# Polarshield_v2_5.net
KiCad netlist of a schematic drawn in EAGLE
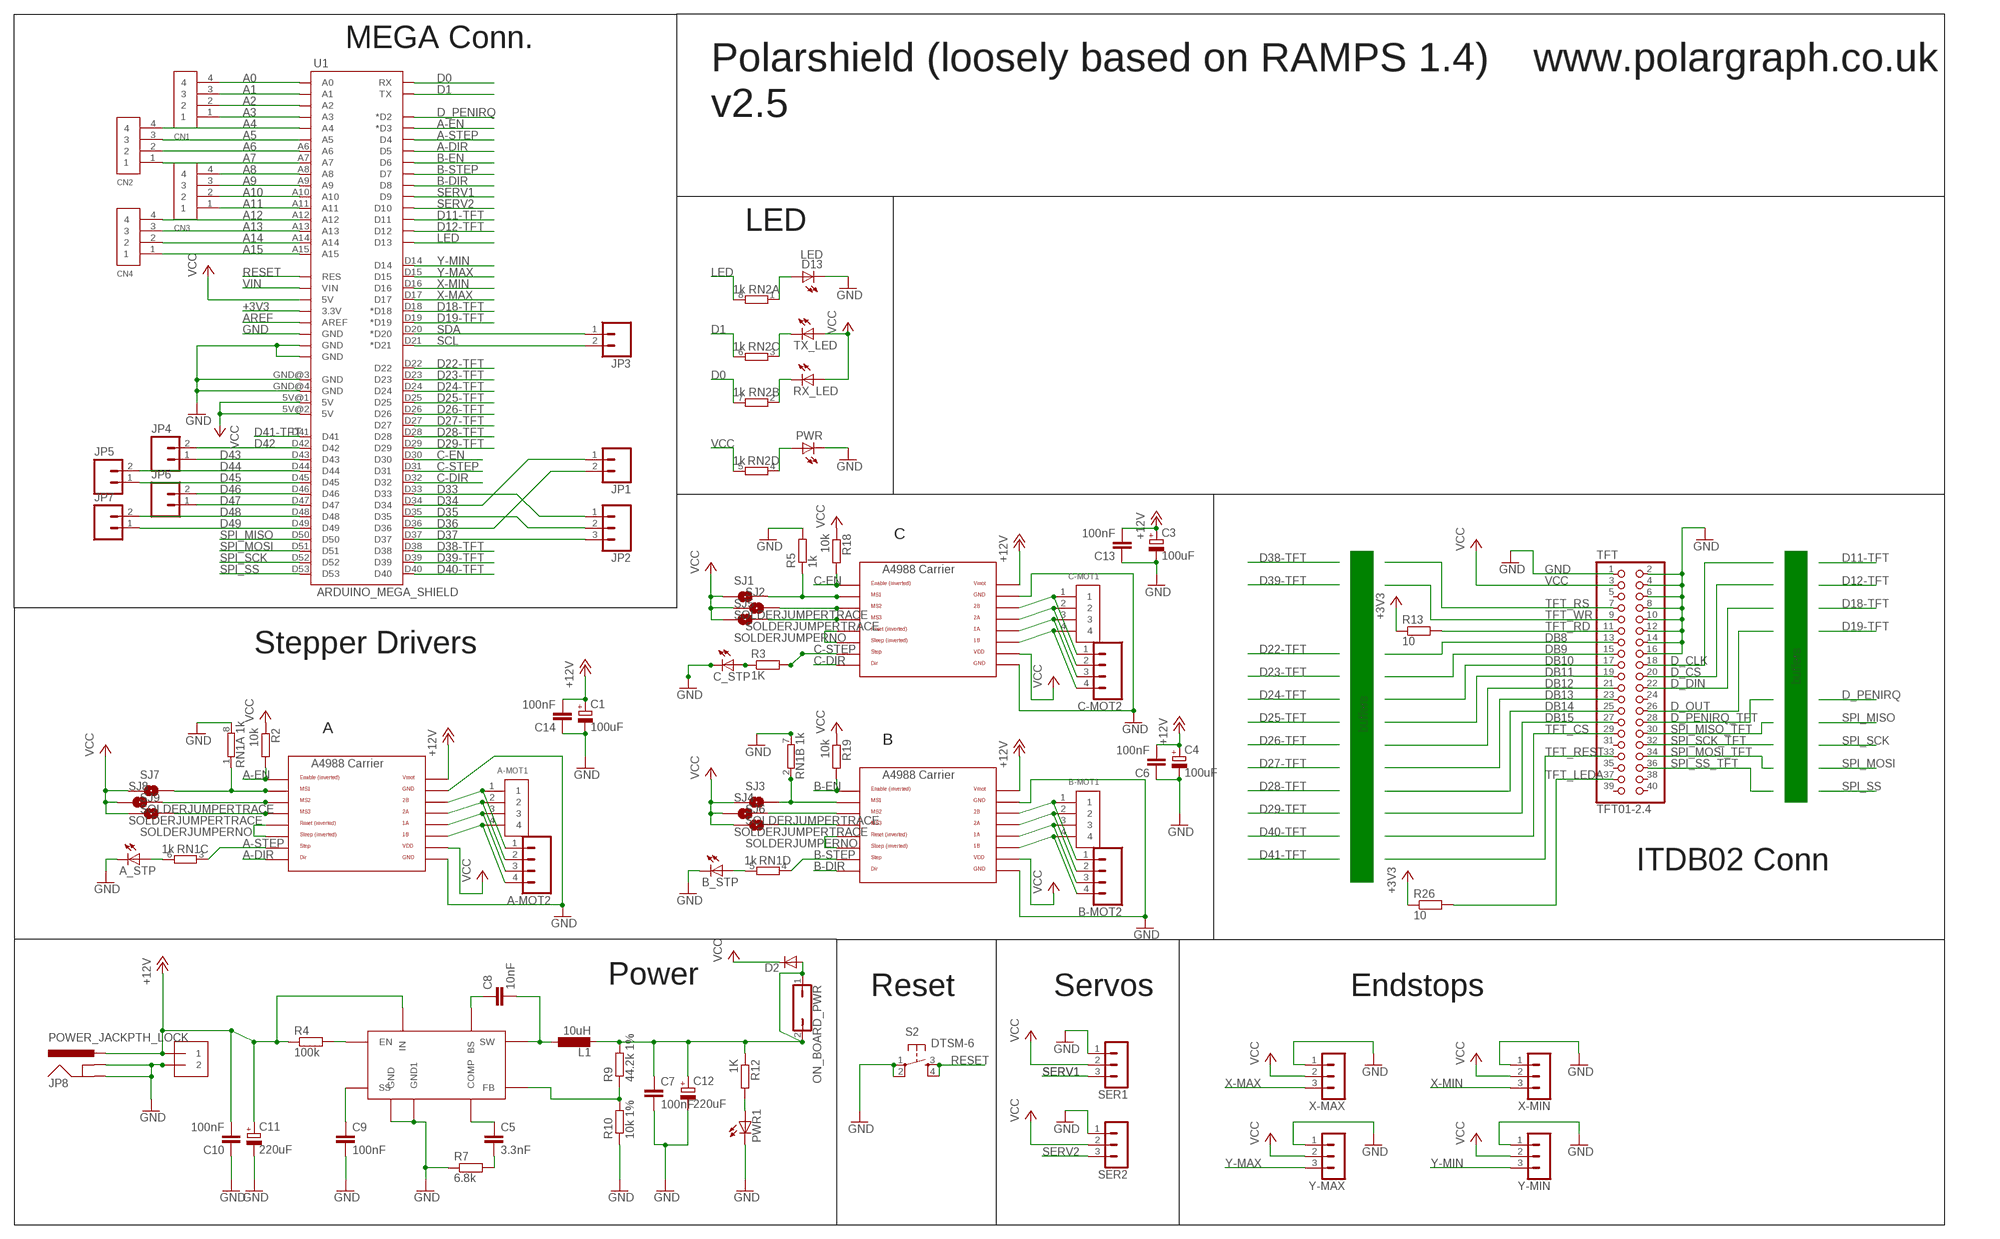
[diagram p0: schematic, sheet 1, part 1 of 2]
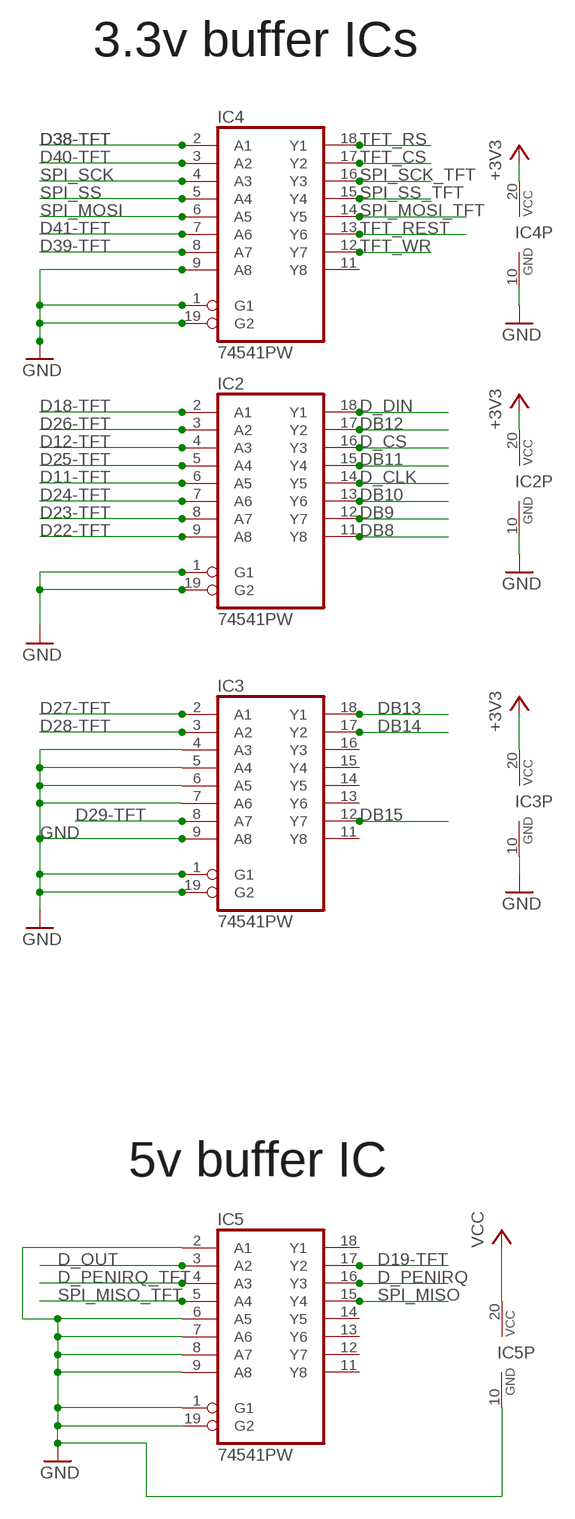
[diagram p1: schematic, sheet 1, part 2 of 2]

(export (version "E")
  (design (tool "Eeschema 10.0.6"))
  (components
    (comp (ref "A-MOT1")
      (value "1X4-BIG")
      (footprint "eagle-import:1X04-BIG")
      (libsource (lib "eagle-import") (part "adafruit_1X4-BIG"))
    )
    (comp (ref "A-MOT2")
      (value "M04SCREW")
      (footprint "eagle-import:SCREWTERMINAL-3.5MM-4")
      (libsource (lib "eagle-import") (part "M04SCREW"))
    )
    (comp (ref "A_STP")
      (value "LEDCHIP-LED0805")
      (footprint "eagle-import:CHIP-LED0805")
      (libsource (lib "eagle-import") (part "LEDCHIP-LED0805"))
    )
    (comp (ref "B-MOT1")
      (value "1X4-BIG")
      (footprint "eagle-import:1X04-BIG")
      (libsource (lib "eagle-import") (part "adafruit_1X4-BIG"))
    )
    (comp (ref "B-MOT2")
      (value "M04SCREW")
      (footprint "eagle-import:SCREWTERMINAL-3.5MM-4")
      (libsource (lib "eagle-import") (part "M04SCREW"))
    )
    (comp (ref "B_STP")
      (value "LEDCHIP-LED0805")
      (footprint "eagle-import:CHIP-LED0805")
      (libsource (lib "eagle-import") (part "LEDCHIP-LED0805"))
    )
    (comp (ref "C-MOT1")
      (value "1X4-BIG")
      (footprint "eagle-import:1X04-BIG")
      (libsource (lib "eagle-import") (part "adafruit_1X4-BIG"))
    )
    (comp (ref "C-MOT2")
      (value "M04SCREW")
      (footprint "eagle-import:SCREWTERMINAL-3.5MM-4")
      (libsource (lib "eagle-import") (part "M04SCREW"))
    )
    (comp (ref "C1")
      (value "100uF")
      (footprint "eagle-import:153CLV-0605")
      (libsource (lib "eagle-import") (part "CPOL-EU153CLV-0605"))
    )
    (comp (ref "C3")
      (value "100uF")
      (footprint "eagle-import:153CLV-0605")
      (libsource (lib "eagle-import") (part "CPOL-EU153CLV-0605"))
    )
    (comp (ref "C4")
      (value "100uF")
      (footprint "eagle-import:153CLV-0605")
      (libsource (lib "eagle-import") (part "CPOL-EU153CLV-0605"))
    )
    (comp (ref "C5")
      (value "3.3nF")
      (footprint "eagle-import:C0805K")
      (libsource (lib "eagle-import") (part "C-EUC0805K"))
    )
    (comp (ref "C6")
      (value "100nF")
      (footprint "eagle-import:C0805")
      (libsource (lib "eagle-import") (part "C-EUC0805"))
    )
    (comp (ref "C7")
      (value "100nF")
      (footprint "eagle-import:C0805K")
      (libsource (lib "eagle-import") (part "C-EUC0805K"))
    )
    (comp (ref "C8")
      (value "10nF")
      (footprint "eagle-import:C0805K")
      (libsource (lib "eagle-import") (part "C-EUC0805K"))
    )
    (comp (ref "C9")
      (value "100nF")
      (footprint "eagle-import:C0805K")
      (libsource (lib "eagle-import") (part "C-EUC0805K"))
    )
    (comp (ref "C10")
      (value "100nF")
      (footprint "eagle-import:C0805K")
      (libsource (lib "eagle-import") (part "C-EUC0805K"))
    )
    (comp (ref "C11")
      (value "220uF")
      (footprint "eagle-import:153CLV-0807")
      (libsource (lib "eagle-import") (part "resistor_CPOL-EU153CLV-0807"))
    )
    (comp (ref "C12")
      (value "220uF")
      (footprint "eagle-import:153CLV-0807")
      (libsource (lib "eagle-import") (part "resistor_CPOL-EU153CLV-0807"))
    )
    (comp (ref "C13")
      (value "100nF")
      (footprint "eagle-import:C0805")
      (libsource (lib "eagle-import") (part "C-EUC0805"))
    )
    (comp (ref "C14")
      (value "100nF")
      (footprint "eagle-import:C0805")
      (libsource (lib "eagle-import") (part "C-EUC0805"))
    )
    (comp (ref "CN1")
      (value "1X4-CLEANBIG")
      (footprint "eagle-import:1X04-CLEANBIG")
      (libsource (lib "eagle-import") (part "1X4-CLEANBIG"))
    )
    (comp (ref "CN2")
      (value "1X4-CLEANBIG")
      (footprint "eagle-import:1X04-CLEANBIG")
      (libsource (lib "eagle-import") (part "1X4-CLEANBIG"))
    )
    (comp (ref "CN3")
      (value "1X4-CLEANBIG")
      (footprint "eagle-import:1X04-CLEANBIG")
      (libsource (lib "eagle-import") (part "1X4-CLEANBIG"))
    )
    (comp (ref "CN4")
      (value "1X4-CLEANBIG")
      (footprint "eagle-import:1X04-CLEANBIG")
      (libsource (lib "eagle-import") (part "1X4-CLEANBIG"))
    )
    (comp (ref "C_STP")
      (value "LEDCHIP-LED0805")
      (footprint "eagle-import:CHIP-LED0805")
      (libsource (lib "eagle-import") (part "LEDCHIP-LED0805"))
    )
    (comp (ref "D2")
      (value "DIODE-DO214BA")
      (footprint "eagle-import:DO214BA")
      (libsource (lib "eagle-import") (part "DIODE-DO214BA"))
    )
    (comp (ref "D13")
      (value "LED")
      (footprint "eagle-import:CHIP-LED0805")
      (libsource (lib "eagle-import") (part "LEDCHIP-LED0805"))
    )
    (comp (ref "IC1")
      (value "MP2307")
      (footprint "eagle-import:SOIC8")
      (libsource (lib "eagle-import") (part "MP2307"))
    )
    (comp (ref "IC2")
      (value "74541PW")
      (footprint "eagle-import:TSSOP20")
      (libsource (lib "eagle-import") (part "74541PW"))
    )
    (comp (ref "IC3")
      (value "74541PW")
      (footprint "eagle-import:TSSOP20")
      (libsource (lib "eagle-import") (part "74541PW"))
    )
    (comp (ref "IC4")
      (value "74541PW")
      (footprint "eagle-import:TSSOP20")
      (libsource (lib "eagle-import") (part "74541PW"))
    )
    (comp (ref "IC5")
      (value "74541PW")
      (footprint "eagle-import:TSSOP20")
      (libsource (lib "eagle-import") (part "74541PW"))
    )
    (comp (ref "J1")
      (value "1X2-3.5MM")
      (footprint "eagle-import:1X2-3.5MM")
      (libsource (lib "eagle-import") (part "1X2-3.5MM"))
    )
    (comp (ref "JP1")
      (value "M021X02_NO_SILK")
      (footprint "eagle-import:1X02_NO_SILK")
      (libsource (lib "eagle-import") (part "M021X02_NO_SILK"))
    )
    (comp (ref "JP2")
      (value "M031X03_NO_SILK")
      (footprint "eagle-import:1X03_NO_SILK")
      (libsource (lib "eagle-import") (part "M031X03_NO_SILK"))
    )
    (comp (ref "JP3")
      (value "M021X02_NO_SILK")
      (footprint "eagle-import:1X02_NO_SILK")
      (libsource (lib "eagle-import") (part "M021X02_NO_SILK"))
    )
    (comp (ref "JP4")
      (value "M021X02_NO_SILK")
      (footprint "eagle-import:1X02_NO_SILK")
      (libsource (lib "eagle-import") (part "M021X02_NO_SILK"))
    )
    (comp (ref "JP5")
      (value "M021X02_NO_SILK")
      (footprint "eagle-import:1X02_NO_SILK")
      (libsource (lib "eagle-import") (part "M021X02_NO_SILK"))
    )
    (comp (ref "JP6")
      (value "M021X02_NO_SILK")
      (footprint "eagle-import:1X02_NO_SILK")
      (libsource (lib "eagle-import") (part "M021X02_NO_SILK"))
    )
    (comp (ref "JP7")
      (value "M021X02_NO_SILK")
      (footprint "eagle-import:1X02_NO_SILK")
      (libsource (lib "eagle-import") (part "M021X02_NO_SILK"))
    )
    (comp (ref "JP8")
      (value "POWER_JACKPTH_LOCK")
      (footprint "eagle-import:POWER_JACK_PTH_LOCK")
      (libsource (lib "eagle-import") (part "POWER_JACKPTH_LOCK"))
    )
    (comp (ref "L1")
      (value "10uH")
      (footprint "eagle-import:PIS2816")
      (libsource (lib "eagle-import") (part "L-EUPIS2816"))
    )
    (comp (ref "ON_BOARD_PWR")
      (value "JP1Q")
      (footprint "eagle-import:JP1")
      (libsource (lib "eagle-import") (part "JP1Q"))
    )
    (comp (ref "PWR")
      (value "LEDCHIP-LED0805")
      (footprint "eagle-import:CHIP-LED0805")
      (libsource (lib "eagle-import") (part "LEDCHIP-LED0805"))
    )
    (comp (ref "PWR1")
      (value "LEDCHIP-LED0805")
      (footprint "eagle-import:CHIP-LED0805")
      (libsource (lib "eagle-import") (part "LEDCHIP-LED0805"))
    )
    (comp (ref "R2")
      (value "10k")
      (footprint "eagle-import:R0805")
      (libsource (lib "eagle-import") (part "R-EU_R0805"))
    )
    (comp (ref "R3")
      (value "1K")
      (footprint "eagle-import:R0805")
      (libsource (lib "eagle-import") (part "R-EU_R0805"))
    )
    (comp (ref "R4")
      (value "100k")
      (footprint "eagle-import:R0805")
      (libsource (lib "eagle-import") (part "resistor_R-EU_R0805"))
    )
    (comp (ref "R5")
      (value "1k")
      (footprint "eagle-import:R0805")
      (libsource (lib "eagle-import") (part "R-EU_R0805"))
    )
    (comp (ref "R7")
      (value "6.8k")
      (footprint "eagle-import:R0805")
      (libsource (lib "eagle-import") (part "resistor_R-EU_R0805"))
    )
    (comp (ref "R9")
      (value "44.2k 1%")
      (footprint "eagle-import:R0805")
      (libsource (lib "eagle-import") (part "resistor_R-EU_R0805"))
    )
    (comp (ref "R10")
      (value "10k 1%")
      (footprint "eagle-import:R0805")
      (libsource (lib "eagle-import") (part "resistor_R-EU_R0805"))
    )
    (comp (ref "R12")
      (value "1K")
      (footprint "eagle-import:R0805")
      (libsource (lib "eagle-import") (part "R-EU_R0805"))
    )
    (comp (ref "R13")
      (value "10")
      (footprint "eagle-import:R0805")
      (libsource (lib "eagle-import") (part "resistor_R-EU_R0805"))
    )
    (comp (ref "R18")
      (value "10k")
      (footprint "eagle-import:R0805")
      (libsource (lib "eagle-import") (part "R-EU_R0805"))
    )
    (comp (ref "R19")
      (value "10k")
      (footprint "eagle-import:R0805")
      (libsource (lib "eagle-import") (part "R-EU_R0805"))
    )
    (comp (ref "R26")
      (value "10")
      (footprint "eagle-import:R0805")
      (libsource (lib "eagle-import") (part "resistor_R-EU_R0805"))
    )
    (comp (ref "RN1")
      (value "1k")
      (footprint "eagle-import:EXBN8V")
      (libsource (lib "eagle-import") (part "4R-NEXBN8V"))
    )
    (comp (ref "RN2")
      (value "1k")
      (footprint "eagle-import:EXBN8V")
      (libsource (lib "eagle-import") (part "4R-NEXBN8V"))
    )
    (comp (ref "RX_LED")
      (value "LEDCHIP-LED0805")
      (footprint "eagle-import:CHIP-LED0805")
      (libsource (lib "eagle-import") (part "LEDCHIP-LED0805"))
    )
    (comp (ref "S2")
      (value "DTSM-6")
      (footprint "eagle-import:DTSM-6")
      (libsource (lib "eagle-import") (part "DTSM-6"))
    )
    (comp (ref "SER1")
      (value "3PIN-HEADER")
      (footprint "eagle-import:3PIN-HEADER")
      (libsource (lib "eagle-import") (part "3PIN-HEADER"))
    )
    (comp (ref "SER2")
      (value "3PIN-HEADER")
      (footprint "eagle-import:3PIN-HEADER")
      (libsource (lib "eagle-import") (part "3PIN-HEADER"))
    )
    (comp (ref "SJ1")
      (value "SOLDERJUMPERTRACE")
      (footprint "eagle-import:SJ_2S-TRACE")
      (libsource (lib "eagle-import") (part "SOLDERJUMPERTRACE"))
    )
    (comp (ref "SJ2")
      (value "SOLDERJUMPERTRACE")
      (footprint "eagle-import:SJ_2S-TRACE")
      (libsource (lib "eagle-import") (part "SOLDERJUMPERTRACE"))
    )
    (comp (ref "SJ3")
      (value "SOLDERJUMPERTRACE")
      (footprint "eagle-import:SJ_2S-TRACE")
      (libsource (lib "eagle-import") (part "SOLDERJUMPERTRACE"))
    )
    (comp (ref "SJ4")
      (value "SOLDERJUMPERTRACE")
      (footprint "eagle-import:SJ_2S-TRACE")
      (libsource (lib "eagle-import") (part "SOLDERJUMPERTRACE"))
    )
    (comp (ref "SJ5")
      (value "SOLDERJUMPERNO")
      (footprint "eagle-import:SJ_2S-NO")
      (libsource (lib "eagle-import") (part "SOLDERJUMPERNO"))
    )
    (comp (ref "SJ6")
      (value "SOLDERJUMPERNO")
      (footprint "eagle-import:SJ_2S-NO")
      (libsource (lib "eagle-import") (part "SOLDERJUMPERNO"))
    )
    (comp (ref "SJ7")
      (value "SOLDERJUMPERTRACE")
      (footprint "eagle-import:SJ_2S-TRACE")
      (libsource (lib "eagle-import") (part "SOLDERJUMPERTRACE"))
    )
    (comp (ref "SJ8")
      (value "SOLDERJUMPERTRACE")
      (footprint "eagle-import:SJ_2S-TRACE")
      (libsource (lib "eagle-import") (part "SOLDERJUMPERTRACE"))
    )
    (comp (ref "SJ9")
      (value "SOLDERJUMPERNO")
      (footprint "eagle-import:SJ_2S-NO")
      (libsource (lib "eagle-import") (part "SOLDERJUMPERNO"))
    )
    (comp (ref "TFT")
      (value "TFT01-2.4")
      (footprint "eagle-import:TFT01-2.4")
      (libsource (lib "eagle-import") (part "TFT01-2.4"))
    )
    (comp (ref "TX_LED")
      (value "LEDCHIP-LED0805")
      (footprint "eagle-import:CHIP-LED0805")
      (libsource (lib "eagle-import") (part "LEDCHIP-LED0805"))
    )
    (comp (ref "U$1")
      (value "A4988BREAKOUT")
      (footprint "eagle-import:A4988BREAKOUT")
      (libsource (lib "eagle-import") (part "A4988BREAKOUT"))
    )
    (comp (ref "U$6")
      (value "A4988BREAKOUT")
      (footprint "eagle-import:A4988BREAKOUT")
      (libsource (lib "eagle-import") (part "A4988BREAKOUT"))
    )
    (comp (ref "U$7")
      (value "A4988BREAKOUT")
      (footprint "eagle-import:A4988BREAKOUT")
      (libsource (lib "eagle-import") (part "A4988BREAKOUT"))
    )
    (comp (ref "U1")
      (value "ARDUINO_MEGA_SHIELD")
      (footprint "eagle-import:ARDUINO_MEGA_SHIELD")
      (libsource (lib "eagle-import") (part "ARDUINO_MEGA_SHIELD"))
    )
    (comp (ref "X-MAX")
      (value "3PIN-HEADER")
      (footprint "eagle-import:3PIN-HEADER")
      (libsource (lib "eagle-import") (part "3PIN-HEADER"))
    )
    (comp (ref "X-MIN")
      (value "3PIN-HEADER")
      (footprint "eagle-import:3PIN-HEADER")
      (libsource (lib "eagle-import") (part "3PIN-HEADER"))
    )
    (comp (ref "Y-MAX")
      (value "3PIN-HEADER")
      (footprint "eagle-import:3PIN-HEADER")
      (libsource (lib "eagle-import") (part "3PIN-HEADER"))
    )
    (comp (ref "Y-MIN")
      (value "3PIN-HEADER")
      (footprint "eagle-import:3PIN-HEADER")
      (libsource (lib "eagle-import") (part "3PIN-HEADER"))
    )
  )
  (nets
    (net (code "1") (name "+3V3") (class "Default")
      (node (ref "IC2") (pin "20") (pinfunction "VCC_20") (pintype "power_in"))
      (node (ref "IC3") (pin "20") (pinfunction "VCC_20") (pintype "power_in"))
      (node (ref "IC4") (pin "20") (pinfunction "VCC_20") (pintype "power_in"))
      (node (ref "R13") (pin "1") (pinfunction "1_1") (pintype "passive"))
      (node (ref "R26") (pin "1") (pinfunction "1_1") (pintype "passive"))
      (node (ref "U1") (pin "3.3V") (pinfunction "3.3V_3.3V") (pintype "bidirectional"))
    )
    (net (code "2") (name "+12V") (class "Default")
      (node (ref "C1") (pin "+") (pinfunction "+_+") (pintype "passive"))
      (node (ref "C10") (pin "2") (pinfunction "2_2") (pintype "passive"))
      (node (ref "C11") (pin "+") (pinfunction "+_+") (pintype "passive"))
      (node (ref "C13") (pin "2") (pinfunction "2_2") (pintype "passive"))
      (node (ref "C14") (pin "2") (pinfunction "2_2") (pintype "passive"))
      (node (ref "C3") (pin "+") (pinfunction "+_+") (pintype "passive"))
      (node (ref "C4") (pin "+") (pinfunction "+_+") (pintype "passive"))
      (node (ref "C6") (pin "2") (pinfunction "2_2") (pintype "passive"))
      (node (ref "IC1") (pin "IN") (pinfunction "IN_IN") (pintype "bidirectional"))
      (node (ref "J1") (pin "1") (pinfunction "1_1") (pintype "passive"))
      (node (ref "JP8") (pin "PWR") (pinfunction "PWR_PWR") (pintype "bidirectional"))
      (node (ref "R4") (pin "1") (pinfunction "1_1") (pintype "passive"))
      (node (ref "U$1") (pin "VMOT") (pinfunction "VMOT_VMOT") (pintype "power_in"))
      (node (ref "U$6") (pin "VMOT") (pinfunction "VMOT_VMOT") (pintype "power_in"))
      (node (ref "U$7") (pin "VMOT") (pinfunction "VMOT_VMOT") (pintype "power_in"))
    )
    (net (code "3") (name "/A-DIR") (class "Default")
      (node (ref "U$1") (pin "DIR") (pinfunction "DIR_DIR") (pintype "input"))
      (node (ref "U1") (pin "D5") (pinfunction "D5_D5") (pintype "bidirectional"))
    )
    (net (code "4") (name "/A-EN") (class "Default")
      (node (ref "R2") (pin "2") (pinfunction "2_2") (pintype "passive"))
      (node (ref "U$1") (pin "EN") (pinfunction "EN_EN") (pintype "input"))
      (node (ref "U1") (pin "D3") (pinfunction "*D3_D3") (pintype "bidirectional"))
    )
    (net (code "5") (name "/A-STEP") (class "Default")
      (node (ref "RN1") (pin "3") (pinfunction "1_3") (pintype "passive"))
      (node (ref "U$1") (pin "STEP") (pinfunction "STEP_STEP") (pintype "input"))
      (node (ref "U1") (pin "D4") (pinfunction "D4_D4") (pintype "bidirectional"))
    )
    (net (code "6") (name "/A0") (class "Default")
      (node (ref "CN1") (pin "4") (pinfunction "4_4") (pintype "bidirectional"))
      (node (ref "U1") (pin "A0") (pinfunction "A0_A0") (pintype "bidirectional"))
    )
    (net (code "7") (name "/A1") (class "Default")
      (node (ref "CN1") (pin "3") (pinfunction "3_3") (pintype "bidirectional"))
      (node (ref "U1") (pin "A1") (pinfunction "A1_A1") (pintype "bidirectional"))
    )
    (net (code "8") (name "/A2") (class "Default")
      (node (ref "CN1") (pin "2") (pinfunction "2_2") (pintype "bidirectional"))
      (node (ref "U1") (pin "A2") (pinfunction "A2_A2") (pintype "bidirectional"))
    )
    (net (code "9") (name "/A3") (class "Default")
      (node (ref "CN1") (pin "1") (pinfunction "1_1") (pintype "bidirectional"))
      (node (ref "U1") (pin "A3") (pinfunction "A3_A3") (pintype "bidirectional"))
    )
    (net (code "10") (name "/A4") (class "Default")
      (node (ref "CN2") (pin "4") (pinfunction "4_4") (pintype "bidirectional"))
      (node (ref "U1") (pin "A4") (pinfunction "A4_A4") (pintype "bidirectional"))
    )
    (net (code "11") (name "/A5") (class "Default")
      (node (ref "CN2") (pin "3") (pinfunction "3_3") (pintype "bidirectional"))
      (node (ref "U1") (pin "A5") (pinfunction "A5_A5") (pintype "bidirectional"))
    )
    (net (code "12") (name "/A6") (class "Default")
      (node (ref "CN2") (pin "2") (pinfunction "2_2") (pintype "bidirectional"))
      (node (ref "U1") (pin "A6") (pinfunction "A6_A6") (pintype "bidirectional"))
    )
    (net (code "13") (name "/A7") (class "Default")
      (node (ref "CN2") (pin "1") (pinfunction "1_1") (pintype "bidirectional"))
      (node (ref "U1") (pin "A7") (pinfunction "A7_A7") (pintype "bidirectional"))
    )
    (net (code "14") (name "/A8") (class "Default")
      (node (ref "CN3") (pin "4") (pinfunction "4_4") (pintype "bidirectional"))
      (node (ref "U1") (pin "A8") (pinfunction "A8_A8") (pintype "bidirectional"))
    )
    (net (code "15") (name "/A9") (class "Default")
      (node (ref "CN3") (pin "3") (pinfunction "3_3") (pintype "bidirectional"))
      (node (ref "U1") (pin "A9") (pinfunction "A9_A9") (pintype "bidirectional"))
    )
    (net (code "16") (name "/A10") (class "Default")
      (node (ref "CN3") (pin "2") (pinfunction "2_2") (pintype "bidirectional"))
      (node (ref "U1") (pin "A10") (pinfunction "A10_A10") (pintype "bidirectional"))
    )
    (net (code "17") (name "/A11") (class "Default")
      (node (ref "CN3") (pin "1") (pinfunction "1_1") (pintype "bidirectional"))
      (node (ref "U1") (pin "A11") (pinfunction "A11_A11") (pintype "bidirectional"))
    )
    (net (code "18") (name "/A12") (class "Default")
      (node (ref "CN4") (pin "4") (pinfunction "4_4") (pintype "bidirectional"))
      (node (ref "U1") (pin "A12") (pinfunction "A12_A12") (pintype "bidirectional"))
    )
    (net (code "19") (name "/A13") (class "Default")
      (node (ref "CN4") (pin "3") (pinfunction "3_3") (pintype "bidirectional"))
      (node (ref "U1") (pin "A13") (pinfunction "A13_A13") (pintype "bidirectional"))
    )
    (net (code "20") (name "/A14") (class "Default")
      (node (ref "CN4") (pin "2") (pinfunction "2_2") (pintype "bidirectional"))
      (node (ref "U1") (pin "A14") (pinfunction "A14_A14") (pintype "bidirectional"))
    )
    (net (code "21") (name "/A15") (class "Default")
      (node (ref "CN4") (pin "1") (pinfunction "1_1") (pintype "bidirectional"))
      (node (ref "U1") (pin "A15") (pinfunction "A15_A15") (pintype "bidirectional"))
    )
    (net (code "22") (name "/AREF") (class "Default")
      (node (ref "U1") (pin "AREF") (pinfunction "AREF_AREF") (pintype "bidirectional"))
    )
    (net (code "23") (name "/B-DIR") (class "Default")
      (node (ref "U$7") (pin "DIR") (pinfunction "DIR_DIR") (pintype "input"))
      (node (ref "U1") (pin "D8") (pinfunction "D8_D8") (pintype "bidirectional"))
    )
    (net (code "24") (name "/B-EN") (class "Default")
      (node (ref "R19") (pin "2") (pinfunction "2_2") (pintype "passive"))
      (node (ref "U$7") (pin "EN") (pinfunction "EN_EN") (pintype "input"))
      (node (ref "U1") (pin "D6") (pinfunction "D6_D6") (pintype "bidirectional"))
    )
    (net (code "25") (name "/B-STEP") (class "Default")
      (node (ref "RN1") (pin "4") (pinfunction "1_4") (pintype "passive"))
      (node (ref "U$7") (pin "STEP") (pinfunction "STEP_STEP") (pintype "input"))
      (node (ref "U1") (pin "D7") (pinfunction "D7_D7") (pintype "bidirectional"))
    )
    (net (code "26") (name "/C-DIR") (class "Default")
      (node (ref "U$6") (pin "DIR") (pinfunction "DIR_DIR") (pintype "input"))
      (node (ref "U1") (pin "D32") (pinfunction "D32_D32") (pintype "bidirectional"))
    )
    (net (code "27") (name "/C-EN") (class "Default")
      (node (ref "R18") (pin "2") (pinfunction "2_2") (pintype "passive"))
      (node (ref "U$6") (pin "EN") (pinfunction "EN_EN") (pintype "input"))
      (node (ref "U1") (pin "D30") (pinfunction "D30_D30") (pintype "bidirectional"))
    )
    (net (code "28") (name "/C-STEP") (class "Default")
      (node (ref "R3") (pin "2") (pinfunction "2_2") (pintype "passive"))
      (node (ref "U$6") (pin "STEP") (pinfunction "STEP_STEP") (pintype "input"))
      (node (ref "U1") (pin "D31") (pinfunction "D31_D31") (pintype "bidirectional"))
    )
    (net (code "29") (name "/D0") (class "Default")
      (node (ref "RN2") (pin "7") (pinfunction "2_7") (pintype "passive"))
      (node (ref "U1") (pin "RX") (pinfunction "RX_RX") (pintype "bidirectional"))
    )
    (net (code "30") (name "/D1") (class "Default")
      (node (ref "RN2") (pin "6") (pinfunction "2_6") (pintype "passive"))
      (node (ref "U1") (pin "TX") (pinfunction "TX_TX") (pintype "bidirectional"))
    )
    (net (code "31") (name "/D11-TFT") (class "Default")
      (node (ref "IC2") (pin "6") (pinfunction "A5_6") (pintype "input"))
      (node (ref "U1") (pin "D11") (pinfunction "D11_D11") (pintype "bidirectional"))
    )
    (net (code "32") (name "/D12-TFT") (class "Default")
      (node (ref "IC2") (pin "4") (pinfunction "A3_4") (pintype "input"))
      (node (ref "U1") (pin "D12") (pinfunction "D12_D12") (pintype "bidirectional"))
    )
    (net (code "33") (name "/D18-TFT") (class "Default")
      (node (ref "IC2") (pin "2") (pinfunction "A1_2") (pintype "input"))
      (node (ref "U1") (pin "D18") (pinfunction "*D18_D18") (pintype "bidirectional"))
    )
    (net (code "34") (name "/D19-TFT") (class "Default")
      (node (ref "IC5") (pin "17") (pinfunction "Y2_17") (pintype "tri_state"))
      (node (ref "U1") (pin "D19") (pinfunction "*D19_D19") (pintype "bidirectional"))
    )
    (net (code "35") (name "/D22-TFT") (class "Default")
      (node (ref "IC2") (pin "9") (pinfunction "A8_9") (pintype "input"))
      (node (ref "U1") (pin "D22") (pinfunction "D22_D22") (pintype "bidirectional"))
    )
    (net (code "36") (name "/D23-TFT") (class "Default")
      (node (ref "IC2") (pin "8") (pinfunction "A7_8") (pintype "input"))
      (node (ref "U1") (pin "D23") (pinfunction "D23_D23") (pintype "bidirectional"))
    )
    (net (code "37") (name "/D24-TFT") (class "Default")
      (node (ref "IC2") (pin "7") (pinfunction "A6_7") (pintype "input"))
      (node (ref "U1") (pin "D24") (pinfunction "D24_D24") (pintype "bidirectional"))
    )
    (net (code "38") (name "/D25-TFT") (class "Default")
      (node (ref "IC2") (pin "5") (pinfunction "A4_5") (pintype "input"))
      (node (ref "U1") (pin "D25") (pinfunction "D25_D25") (pintype "bidirectional"))
    )
    (net (code "39") (name "/D26-TFT") (class "Default")
      (node (ref "IC2") (pin "3") (pinfunction "A2_3") (pintype "input"))
      (node (ref "U1") (pin "D26") (pinfunction "D26_D26") (pintype "bidirectional"))
    )
    (net (code "40") (name "/D27-TFT") (class "Default")
      (node (ref "IC3") (pin "2") (pinfunction "A1_2") (pintype "input"))
      (node (ref "U1") (pin "D27") (pinfunction "D27_D27") (pintype "bidirectional"))
    )
    (net (code "41") (name "/D28-TFT") (class "Default")
      (node (ref "IC3") (pin "3") (pinfunction "A2_3") (pintype "input"))
      (node (ref "U1") (pin "D28") (pinfunction "D28_D28") (pintype "bidirectional"))
    )
    (net (code "42") (name "/D29-TFT") (class "Default")
      (node (ref "IC3") (pin "8") (pinfunction "A7_8") (pintype "input"))
      (node (ref "U1") (pin "D29") (pinfunction "D29_D29") (pintype "bidirectional"))
    )
    (net (code "43") (name "/D33") (class "Default")
      (node (ref "JP2") (pin "1") (pinfunction "1_1") (pintype "passive"))
      (node (ref "U1") (pin "D33") (pinfunction "D33_D33") (pintype "bidirectional"))
    )
    (net (code "44") (name "/D34") (class "Default")
      (node (ref "JP1") (pin "1") (pinfunction "1_1") (pintype "passive"))
      (node (ref "U1") (pin "D34") (pinfunction "D34_D34") (pintype "bidirectional"))
    )
    (net (code "45") (name "/D35") (class "Default")
      (node (ref "JP2") (pin "2") (pinfunction "2_2") (pintype "passive"))
      (node (ref "U1") (pin "D35") (pinfunction "D35_D35") (pintype "bidirectional"))
    )
    (net (code "46") (name "/D36") (class "Default")
      (node (ref "JP1") (pin "2") (pinfunction "2_2") (pintype "passive"))
      (node (ref "U1") (pin "D36") (pinfunction "D36_D36") (pintype "bidirectional"))
    )
    (net (code "47") (name "/D37") (class "Default")
      (node (ref "JP2") (pin "3") (pinfunction "3_3") (pintype "passive"))
      (node (ref "U1") (pin "D37") (pinfunction "D37_D37") (pintype "bidirectional"))
    )
    (net (code "48") (name "/D38-TFT") (class "Default")
      (node (ref "IC4") (pin "2") (pinfunction "A1_2") (pintype "input"))
      (node (ref "U1") (pin "D38") (pinfunction "D38_D38") (pintype "bidirectional"))
    )
    (net (code "49") (name "/D39-TFT") (class "Default")
      (node (ref "IC4") (pin "8") (pinfunction "A7_8") (pintype "input"))
      (node (ref "U1") (pin "D39") (pinfunction "D39_D39") (pintype "bidirectional"))
    )
    (net (code "50") (name "/D40-TFT") (class "Default")
      (node (ref "IC4") (pin "3") (pinfunction "A2_3") (pintype "input"))
      (node (ref "U1") (pin "D40") (pinfunction "D40_D40") (pintype "bidirectional"))
    )
    (net (code "51") (name "/D41-TFT") (class "Default")
      (node (ref "IC4") (pin "7") (pinfunction "A6_7") (pintype "input"))
      (node (ref "U1") (pin "D41") (pinfunction "D41_D41") (pintype "bidirectional"))
    )
    (net (code "52") (name "/D42") (class "Default")
      (node (ref "JP4") (pin "2") (pinfunction "2_2") (pintype "passive"))
      (node (ref "U1") (pin "D42") (pinfunction "D42_D42") (pintype "bidirectional"))
    )
    (net (code "53") (name "/D43") (class "Default")
      (node (ref "JP4") (pin "1") (pinfunction "1_1") (pintype "passive"))
      (node (ref "U1") (pin "D43") (pinfunction "D43_D43") (pintype "bidirectional"))
    )
    (net (code "54") (name "/D44") (class "Default")
      (node (ref "JP5") (pin "2") (pinfunction "2_2") (pintype "passive"))
      (node (ref "U1") (pin "D44") (pinfunction "D44_D44") (pintype "bidirectional"))
    )
    (net (code "55") (name "/D45") (class "Default")
      (node (ref "JP5") (pin "1") (pinfunction "1_1") (pintype "passive"))
      (node (ref "U1") (pin "D45") (pinfunction "D45_D45") (pintype "bidirectional"))
    )
    (net (code "56") (name "/D46") (class "Default")
      (node (ref "JP6") (pin "2") (pinfunction "2_2") (pintype "passive"))
      (node (ref "U1") (pin "D46") (pinfunction "D46_D46") (pintype "bidirectional"))
    )
    (net (code "57") (name "/D47") (class "Default")
      (node (ref "JP6") (pin "1") (pinfunction "1_1") (pintype "passive"))
      (node (ref "U1") (pin "D47") (pinfunction "D47_D47") (pintype "bidirectional"))
    )
    (net (code "58") (name "/D48") (class "Default")
      (node (ref "JP7") (pin "2") (pinfunction "2_2") (pintype "passive"))
      (node (ref "U1") (pin "D48") (pinfunction "D48_D48") (pintype "bidirectional"))
    )
    (net (code "59") (name "/D49") (class "Default")
      (node (ref "JP7") (pin "1") (pinfunction "1_1") (pintype "passive"))
      (node (ref "U1") (pin "D49") (pinfunction "D49_D49") (pintype "bidirectional"))
    )
    (net (code "60") (name "/DB8") (class "Default")
      (node (ref "IC2") (pin "11") (pinfunction "Y8_11") (pintype "tri_state"))
      (node (ref "TFT") (pin "13") (pinfunction "13_13") (pintype "passive"))
    )
    (net (code "61") (name "/DB9") (class "Default")
      (node (ref "IC2") (pin "12") (pinfunction "Y7_12") (pintype "tri_state"))
      (node (ref "TFT") (pin "15") (pinfunction "15_15") (pintype "passive"))
    )
    (net (code "62") (name "/DB10") (class "Default")
      (node (ref "IC2") (pin "13") (pinfunction "Y6_13") (pintype "tri_state"))
      (node (ref "TFT") (pin "17") (pinfunction "17_17") (pintype "passive"))
    )
    (net (code "63") (name "/DB11") (class "Default")
      (node (ref "IC2") (pin "15") (pinfunction "Y4_15") (pintype "tri_state"))
      (node (ref "TFT") (pin "19") (pinfunction "19_19") (pintype "passive"))
    )
    (net (code "64") (name "/DB12") (class "Default")
      (node (ref "IC2") (pin "17") (pinfunction "Y2_17") (pintype "tri_state"))
      (node (ref "TFT") (pin "21") (pinfunction "21_21") (pintype "passive"))
    )
    (net (code "65") (name "/DB13") (class "Default")
      (node (ref "IC3") (pin "18") (pinfunction "Y1_18") (pintype "tri_state"))
      (node (ref "TFT") (pin "23") (pinfunction "23_23") (pintype "passive"))
    )
    (net (code "66") (name "/DB14") (class "Default")
      (node (ref "IC3") (pin "17") (pinfunction "Y2_17") (pintype "tri_state"))
      (node (ref "TFT") (pin "25") (pinfunction "25_25") (pintype "passive"))
    )
    (net (code "67") (name "/DB15") (class "Default")
      (node (ref "IC3") (pin "12") (pinfunction "Y7_12") (pintype "tri_state"))
      (node (ref "TFT") (pin "27") (pinfunction "27_27") (pintype "passive"))
    )
    (net (code "68") (name "/D_CLK") (class "Default")
      (node (ref "IC2") (pin "14") (pinfunction "Y5_14") (pintype "tri_state"))
      (node (ref "TFT") (pin "18") (pinfunction "18_18") (pintype "passive"))
    )
    (net (code "69") (name "/D_CS") (class "Default")
      (node (ref "IC2") (pin "16") (pinfunction "Y3_16") (pintype "tri_state"))
      (node (ref "TFT") (pin "20") (pinfunction "20_20") (pintype "passive"))
    )
    (net (code "70") (name "/D_DIN") (class "Default")
      (node (ref "IC2") (pin "18") (pinfunction "Y1_18") (pintype "tri_state"))
      (node (ref "TFT") (pin "22") (pinfunction "22_22") (pintype "passive"))
    )
    (net (code "71") (name "/D_OUT") (class "Default")
      (node (ref "IC5") (pin "3") (pinfunction "A2_3") (pintype "input"))
      (node (ref "TFT") (pin "26") (pinfunction "26_26") (pintype "passive"))
    )
    (net (code "72") (name "/D_PENIRQ") (class "Default")
      (node (ref "IC5") (pin "16") (pinfunction "Y3_16") (pintype "tri_state"))
      (node (ref "U1") (pin "D2") (pinfunction "*D2_D2") (pintype "bidirectional"))
    )
    (net (code "73") (name "/D_PENIRQ_TFT") (class "Default")
      (node (ref "IC5") (pin "4") (pinfunction "A3_4") (pintype "input"))
      (node (ref "TFT") (pin "28") (pinfunction "28_28") (pintype "passive"))
    )
    (net (code "74") (name "/LED") (class "Default")
      (node (ref "RN2") (pin "8") (pinfunction "2_8") (pintype "passive"))
      (node (ref "U1") (pin "D13") (pinfunction "D13_D13") (pintype "bidirectional"))
    )
    (net (code "75") (name "/RESET") (class "Default")
      (node (ref "S2") (pin "3") (pinfunction "3_3") (pintype "passive"))
      (node (ref "S2") (pin "4") (pinfunction "4_4") (pintype "passive"))
      (node (ref "U1") (pin "RES") (pinfunction "RES_RES") (pintype "bidirectional"))
    )
    (net (code "76") (name "/SCL") (class "Default")
      (node (ref "JP3") (pin "2") (pinfunction "2_2") (pintype "passive"))
      (node (ref "U1") (pin "D21") (pinfunction "*D21_D21") (pintype "bidirectional"))
    )
    (net (code "77") (name "/SDA") (class "Default")
      (node (ref "JP3") (pin "1") (pinfunction "1_1") (pintype "passive"))
      (node (ref "U1") (pin "D20") (pinfunction "*D20_D20") (pintype "bidirectional"))
    )
    (net (code "78") (name "/SERV1") (class "Default")
      (node (ref "SER1") (pin "3") (pinfunction "3_3") (pintype "passive"))
      (node (ref "U1") (pin "D9") (pinfunction "D9_D9") (pintype "bidirectional"))
    )
    (net (code "79") (name "/SERV2") (class "Default")
      (node (ref "SER2") (pin "3") (pinfunction "3_3") (pintype "passive"))
      (node (ref "U1") (pin "D10") (pinfunction "D10_D10") (pintype "bidirectional"))
    )
    (net (code "80") (name "/SPI_MISO") (class "Default")
      (node (ref "IC5") (pin "15") (pinfunction "Y4_15") (pintype "tri_state"))
      (node (ref "U1") (pin "D50") (pinfunction "D50_D50") (pintype "bidirectional"))
    )
    (net (code "81") (name "/SPI_MISO_TFT") (class "Default")
      (node (ref "IC5") (pin "5") (pinfunction "A4_5") (pintype "input"))
      (node (ref "TFT") (pin "30") (pinfunction "30_30") (pintype "passive"))
    )
    (net (code "82") (name "/SPI_MOSI") (class "Default")
      (node (ref "IC4") (pin "6") (pinfunction "A5_6") (pintype "input"))
      (node (ref "U1") (pin "D51") (pinfunction "D51_D51") (pintype "bidirectional"))
    )
    (net (code "83") (name "/SPI_MOSI_TFT") (class "Default")
      (node (ref "IC4") (pin "14") (pinfunction "Y5_14") (pintype "tri_state"))
      (node (ref "TFT") (pin "34") (pinfunction "34_34") (pintype "passive"))
    )
    (net (code "84") (name "/SPI_SCK") (class "Default")
      (node (ref "IC4") (pin "4") (pinfunction "A3_4") (pintype "input"))
      (node (ref "U1") (pin "D52") (pinfunction "D52_D52") (pintype "bidirectional"))
    )
    (net (code "85") (name "/SPI_SCK_TFT") (class "Default")
      (node (ref "IC4") (pin "16") (pinfunction "Y3_16") (pintype "tri_state"))
      (node (ref "TFT") (pin "32") (pinfunction "32_32") (pintype "passive"))
    )
    (net (code "86") (name "/SPI_SS") (class "Default")
      (node (ref "IC4") (pin "5") (pinfunction "A4_5") (pintype "input"))
      (node (ref "U1") (pin "D53") (pinfunction "D53_D53") (pintype "bidirectional"))
    )
    (net (code "87") (name "/SPI_SS_TFT") (class "Default")
      (node (ref "IC4") (pin "15") (pinfunction "Y4_15") (pintype "tri_state"))
      (node (ref "TFT") (pin "36") (pinfunction "36_36") (pintype "passive"))
    )
    (net (code "88") (name "/TFT_CS") (class "Default")
      (node (ref "IC4") (pin "17") (pinfunction "Y2_17") (pintype "tri_state"))
      (node (ref "TFT") (pin "29") (pinfunction "29_29") (pintype "passive"))
    )
    (net (code "89") (name "/TFT_LEDA") (class "Default")
      (node (ref "R26") (pin "2") (pinfunction "2_2") (pintype "passive"))
      (node (ref "TFT") (pin "37") (pinfunction "37_37") (pintype "passive"))
    )
    (net (code "90") (name "/TFT_RD") (class "Default")
      (node (ref "R13") (pin "2") (pinfunction "2_2") (pintype "passive"))
      (node (ref "TFT") (pin "11") (pinfunction "11_11") (pintype "passive"))
    )
    (net (code "91") (name "/TFT_REST") (class "Default")
      (node (ref "IC4") (pin "13") (pinfunction "Y6_13") (pintype "tri_state"))
      (node (ref "TFT") (pin "33") (pinfunction "33_33") (pintype "passive"))
    )
    (net (code "92") (name "/TFT_RS") (class "Default")
      (node (ref "IC4") (pin "18") (pinfunction "Y1_18") (pintype "tri_state"))
      (node (ref "TFT") (pin "7") (pinfunction "7_7") (pintype "passive"))
    )
    (net (code "93") (name "/TFT_WR") (class "Default")
      (node (ref "IC4") (pin "12") (pinfunction "Y7_12") (pintype "tri_state"))
      (node (ref "TFT") (pin "9") (pinfunction "9_9") (pintype "passive"))
    )
    (net (code "94") (name "/VIN") (class "Default")
      (node (ref "U1") (pin "VIN") (pinfunction "VIN_VIN") (pintype "bidirectional"))
    )
    (net (code "95") (name "/X-MAX") (class "Default")
      (node (ref "U1") (pin "D17") (pinfunction "D17_D17") (pintype "bidirectional"))
      (node (ref "X-MAX") (pin "3") (pinfunction "3_3") (pintype "passive"))
    )
    (net (code "96") (name "/X-MIN") (class "Default")
      (node (ref "U1") (pin "D16") (pinfunction "D16_D16") (pintype "bidirectional"))
      (node (ref "X-MIN") (pin "3") (pinfunction "3_3") (pintype "passive"))
    )
    (net (code "97") (name "/Y-MAX") (class "Default")
      (node (ref "U1") (pin "D15") (pinfunction "D15_D15") (pintype "bidirectional"))
      (node (ref "Y-MAX") (pin "3") (pinfunction "3_3") (pintype "passive"))
    )
    (net (code "98") (name "/Y-MIN") (class "Default")
      (node (ref "U1") (pin "D14") (pinfunction "D14_D14") (pintype "bidirectional"))
      (node (ref "Y-MIN") (pin "3") (pinfunction "3_3") (pintype "passive"))
    )
    (net (code "99") (name "GND") (class "Default")
      (node (ref "A_STP") (pin "C") (pinfunction "C_C") (pintype "passive"))
      (node (ref "B_STP") (pin "C") (pinfunction "C_C") (pintype "passive"))
      (node (ref "C1") (pin "-") (pinfunction "-_-") (pintype "passive"))
      (node (ref "C10") (pin "1") (pinfunction "1_1") (pintype "passive"))
      (node (ref "C11") (pin "-") (pinfunction "-_-") (pintype "passive"))
      (node (ref "C12") (pin "-") (pinfunction "-_-") (pintype "passive"))
      (node (ref "C13") (pin "1") (pinfunction "1_1") (pintype "passive"))
      (node (ref "C14") (pin "1") (pinfunction "1_1") (pintype "passive"))
      (node (ref "C3") (pin "-") (pinfunction "-_-") (pintype "passive"))
      (node (ref "C4") (pin "-") (pinfunction "-_-") (pintype "passive"))
      (node (ref "C6") (pin "1") (pinfunction "1_1") (pintype "passive"))
      (node (ref "C7") (pin "2") (pinfunction "2_2") (pintype "passive"))
      (node (ref "C9") (pin "2") (pinfunction "2_2") (pintype "passive"))
      (node (ref "C_STP") (pin "C") (pinfunction "C_C") (pintype "passive"))
      (node (ref "D13") (pin "C") (pinfunction "C_C") (pintype "passive"))
      (node (ref "IC1") (pin "GND") (pinfunction "GND_GND") (pintype "bidirectional"))
      (node (ref "IC1") (pin "GND1") (pinfunction "GND1_GND1") (pintype "bidirectional"))
      (node (ref "IC2") (pin "1") (pinfunction "G1_1") (pintype "input"))
      (node (ref "IC2") (pin "10") (pinfunction "GND_10") (pintype "power_in"))
      (node (ref "IC2") (pin "19") (pinfunction "G2_19") (pintype "input"))
      (node (ref "IC3") (pin "1") (pinfunction "G1_1") (pintype "input"))
      (node (ref "IC3") (pin "10") (pinfunction "GND_10") (pintype "power_in"))
      (node (ref "IC3") (pin "19") (pinfunction "G2_19") (pintype "input"))
      (node (ref "IC3") (pin "4") (pinfunction "A3_4") (pintype "input"))
      (node (ref "IC3") (pin "5") (pinfunction "A4_5") (pintype "input"))
      (node (ref "IC3") (pin "6") (pinfunction "A5_6") (pintype "input"))
      (node (ref "IC3") (pin "7") (pinfunction "A6_7") (pintype "input"))
      (node (ref "IC3") (pin "9") (pinfunction "A8_9") (pintype "input"))
      (node (ref "IC4") (pin "1") (pinfunction "G1_1") (pintype "input"))
      (node (ref "IC4") (pin "10") (pinfunction "GND_10") (pintype "power_in"))
      (node (ref "IC4") (pin "19") (pinfunction "G2_19") (pintype "input"))
      (node (ref "IC4") (pin "9") (pinfunction "A8_9") (pintype "input"))
      (node (ref "IC5") (pin "1") (pinfunction "G1_1") (pintype "input"))
      (node (ref "IC5") (pin "10") (pinfunction "GND_10") (pintype "power_in"))
      (node (ref "IC5") (pin "19") (pinfunction "G2_19") (pintype "input"))
      (node (ref "IC5") (pin "2") (pinfunction "A1_2") (pintype "input"))
      (node (ref "IC5") (pin "6") (pinfunction "A5_6") (pintype "input"))
      (node (ref "IC5") (pin "7") (pinfunction "A6_7") (pintype "input"))
      (node (ref "IC5") (pin "8") (pinfunction "A7_8") (pintype "input"))
      (node (ref "IC5") (pin "9") (pinfunction "A8_9") (pintype "input"))
      (node (ref "J1") (pin "2") (pinfunction "2_2") (pintype "passive"))
      (node (ref "JP8") (pin "GND") (pinfunction "GND_GND") (pintype "bidirectional"))
      (node (ref "JP8") (pin "GNDBREAK") (pinfunction "GNDBREAK_GNDBREAK") (pintype "bidirectional"))
      (node (ref "PWR") (pin "C") (pinfunction "C_C") (pintype "passive"))
      (node (ref "PWR1") (pin "C") (pinfunction "C_C") (pintype "passive"))
      (node (ref "R10") (pin "1") (pinfunction "1_1") (pintype "passive"))
      (node (ref "R5") (pin "2") (pinfunction "2_2") (pintype "passive"))
      (node (ref "R7") (pin "1") (pinfunction "1_1") (pintype "passive"))
      (node (ref "RN1") (pin "7") (pinfunction "2_7") (pintype "passive"))
      (node (ref "RN1") (pin "8") (pinfunction "2_8") (pintype "passive"))
      (node (ref "S2") (pin "1") (pinfunction "1_1") (pintype "passive"))
      (node (ref "S2") (pin "2") (pinfunction "2_2") (pintype "passive"))
      (node (ref "SER1") (pin "1") (pinfunction "1_1") (pintype "passive"))
      (node (ref "SER2") (pin "1") (pinfunction "1_1") (pintype "passive"))
      (node (ref "TFT") (pin "1") (pinfunction "1_1") (pintype "passive"))
      (node (ref "TFT") (pin "10") (pinfunction "10_10") (pintype "passive"))
      (node (ref "TFT") (pin "12") (pinfunction "12_12") (pintype "passive"))
      (node (ref "TFT") (pin "14") (pinfunction "14_14") (pintype "passive"))
      (node (ref "TFT") (pin "16") (pinfunction "16_16") (pintype "passive"))
      (node (ref "TFT") (pin "2") (pinfunction "2_2") (pintype "passive"))
      (node (ref "TFT") (pin "4") (pinfunction "4_4") (pintype "passive"))
      (node (ref "TFT") (pin "6") (pinfunction "6_6") (pintype "passive"))
      (node (ref "TFT") (pin "8") (pinfunction "8_8") (pintype "passive"))
      (node (ref "U$1") (pin "GND") (pinfunction "GND_GND") (pintype "power_in"))
      (node (ref "U$1") (pin "GND@0") (pinfunction "GND_GND@0") (pintype "power_in"))
      (node (ref "U$6") (pin "GND") (pinfunction "GND_GND") (pintype "power_in"))
      (node (ref "U$6") (pin "GND@0") (pinfunction "GND_GND@0") (pintype "power_in"))
      (node (ref "U$7") (pin "GND") (pinfunction "GND_GND") (pintype "power_in"))
      (node (ref "U$7") (pin "GND@0") (pinfunction "GND_GND@0") (pintype "power_in"))
      (node (ref "U1") (pin "GND@0") (pinfunction "GND_GND@0") (pintype "power_in"))
      (node (ref "U1") (pin "GND@1") (pinfunction "GND_GND@1") (pintype "power_in"))
      (node (ref "U1") (pin "GND@2") (pinfunction "GND_GND@2") (pintype "power_in"))
      (node (ref "U1") (pin "GND@3") (pinfunction "GND_GND@3") (pintype "power_in"))
      (node (ref "U1") (pin "GND@4") (pinfunction "GND_GND@4") (pintype "power_in"))
      (node (ref "X-MAX") (pin "1") (pinfunction "1_1") (pintype "passive"))
      (node (ref "X-MIN") (pin "1") (pinfunction "1_1") (pintype "passive"))
      (node (ref "Y-MAX") (pin "1") (pinfunction "1_1") (pintype "passive"))
      (node (ref "Y-MIN") (pin "1") (pinfunction "1_1") (pintype "passive"))
    )
    (net (code "100") (name "Net-(A-MOT1-Pad1)") (class "Default")
      (node (ref "A-MOT1") (pin "1") (pinfunction "1_1") (pintype "bidirectional"))
      (node (ref "A-MOT2") (pin "1") (pinfunction "1_1") (pintype "passive"))
      (node (ref "U$1") (pin "2B") (pinfunction "2B_2B") (pintype "output"))
    )
    (net (code "101") (name "Net-(A-MOT1-Pad2)") (class "Default")
      (node (ref "A-MOT1") (pin "2") (pinfunction "2_2") (pintype "bidirectional"))
      (node (ref "A-MOT2") (pin "2") (pinfunction "2_2") (pintype "passive"))
      (node (ref "U$1") (pin "2A") (pinfunction "2A_2A") (pintype "output"))
    )
    (net (code "102") (name "Net-(A-MOT1-Pad3)") (class "Default")
      (node (ref "A-MOT1") (pin "3") (pinfunction "3_3") (pintype "bidirectional"))
      (node (ref "A-MOT2") (pin "3") (pinfunction "3_3") (pintype "passive"))
      (node (ref "U$1") (pin "1A") (pinfunction "1A_1A") (pintype "output"))
    )
    (net (code "103") (name "Net-(A-MOT1-Pad4)") (class "Default")
      (node (ref "A-MOT1") (pin "4") (pinfunction "4_4") (pintype "bidirectional"))
      (node (ref "A-MOT2") (pin "4") (pinfunction "4_4") (pintype "passive"))
      (node (ref "U$1") (pin "1B") (pinfunction "1B_1B") (pintype "output"))
    )
    (net (code "104") (name "Net-(B-MOT1-Pad1)") (class "Default")
      (node (ref "B-MOT1") (pin "1") (pinfunction "1_1") (pintype "bidirectional"))
      (node (ref "B-MOT2") (pin "1") (pinfunction "1_1") (pintype "passive"))
      (node (ref "U$7") (pin "2B") (pinfunction "2B_2B") (pintype "output"))
    )
    (net (code "105") (name "Net-(B-MOT1-Pad2)") (class "Default")
      (node (ref "B-MOT1") (pin "2") (pinfunction "2_2") (pintype "bidirectional"))
      (node (ref "B-MOT2") (pin "2") (pinfunction "2_2") (pintype "passive"))
      (node (ref "U$7") (pin "2A") (pinfunction "2A_2A") (pintype "output"))
    )
    (net (code "106") (name "Net-(B-MOT1-Pad3)") (class "Default")
      (node (ref "B-MOT1") (pin "3") (pinfunction "3_3") (pintype "bidirectional"))
      (node (ref "B-MOT2") (pin "3") (pinfunction "3_3") (pintype "passive"))
      (node (ref "U$7") (pin "1A") (pinfunction "1A_1A") (pintype "output"))
    )
    (net (code "107") (name "Net-(B-MOT1-Pad4)") (class "Default")
      (node (ref "B-MOT1") (pin "4") (pinfunction "4_4") (pintype "bidirectional"))
      (node (ref "B-MOT2") (pin "4") (pinfunction "4_4") (pintype "passive"))
      (node (ref "U$7") (pin "1B") (pinfunction "1B_1B") (pintype "output"))
    )
    (net (code "108") (name "Net-(C-MOT1-Pad1)") (class "Default")
      (node (ref "C-MOT1") (pin "1") (pinfunction "1_1") (pintype "bidirectional"))
      (node (ref "C-MOT2") (pin "1") (pinfunction "1_1") (pintype "passive"))
      (node (ref "U$6") (pin "2B") (pinfunction "2B_2B") (pintype "output"))
    )
    (net (code "109") (name "Net-(C-MOT1-Pad2)") (class "Default")
      (node (ref "C-MOT1") (pin "2") (pinfunction "2_2") (pintype "bidirectional"))
      (node (ref "C-MOT2") (pin "2") (pinfunction "2_2") (pintype "passive"))
      (node (ref "U$6") (pin "2A") (pinfunction "2A_2A") (pintype "output"))
    )
    (net (code "110") (name "Net-(C-MOT1-Pad3)") (class "Default")
      (node (ref "C-MOT1") (pin "3") (pinfunction "3_3") (pintype "bidirectional"))
      (node (ref "C-MOT2") (pin "3") (pinfunction "3_3") (pintype "passive"))
      (node (ref "U$6") (pin "1A") (pinfunction "1A_1A") (pintype "output"))
    )
    (net (code "111") (name "Net-(C-MOT1-Pad4)") (class "Default")
      (node (ref "C-MOT1") (pin "4") (pinfunction "4_4") (pintype "bidirectional"))
      (node (ref "C-MOT2") (pin "4") (pinfunction "4_4") (pintype "passive"))
      (node (ref "U$6") (pin "1B") (pinfunction "1B_1B") (pintype "output"))
    )
    (net (code "112") (name "Net-(C5-Pad1)") (class "Default")
      (node (ref "C5") (pin "1") (pinfunction "1_1") (pintype "passive"))
      (node (ref "IC1") (pin "COMP") (pinfunction "COMP_COMP") (pintype "bidirectional"))
    )
    (net (code "113") (name "Net-(C5-Pad2)") (class "Default")
      (node (ref "C5") (pin "2") (pinfunction "2_2") (pintype "passive"))
      (node (ref "R7") (pin "2") (pinfunction "2_2") (pintype "passive"))
    )
    (net (code "114") (name "Net-(C8-Pad1)") (class "Default")
      (node (ref "C8") (pin "1") (pinfunction "1_1") (pintype "passive"))
      (node (ref "IC1") (pin "BS") (pinfunction "BS_BS") (pintype "bidirectional"))
    )
    (net (code "115") (name "Net-(C8-Pad2)") (class "Default")
      (node (ref "C8") (pin "2") (pinfunction "2_2") (pintype "passive"))
      (node (ref "IC1") (pin "SW") (pinfunction "SW_SW") (pintype "bidirectional"))
      (node (ref "L1") (pin "1") (pinfunction "1_1") (pintype "passive"))
    )
    (net (code "116") (name "Net-(C9-Pad1)") (class "Default")
      (node (ref "C9") (pin "1") (pinfunction "1_1") (pintype "passive"))
      (node (ref "IC1") (pin "SS") (pinfunction "SS_SS") (pintype "bidirectional"))
    )
    (net (code "117") (name "Net-(C12-Pad+)") (class "Default")
      (node (ref "C12") (pin "+") (pinfunction "+_+") (pintype "passive"))
      (node (ref "C7") (pin "1") (pinfunction "1_1") (pintype "passive"))
      (node (ref "D2") (pin "A") (pinfunction "A_A") (pintype "passive"))
      (node (ref "L1") (pin "2") (pinfunction "2_2") (pintype "passive"))
      (node (ref "ON_BOARD_PWR") (pin "1") (pinfunction "1_1") (pintype "passive"))
      (node (ref "ON_BOARD_PWR") (pin "2") (pinfunction "2_2") (pintype "passive"))
      (node (ref "R12") (pin "1") (pinfunction "1_1") (pintype "passive"))
      (node (ref "R9") (pin "2") (pinfunction "2_2") (pintype "passive"))
    )
    (net (code "118") (name "Net-(C_STP-PadA)") (class "Default")
      (node (ref "C_STP") (pin "A") (pinfunction "A_A") (pintype "passive"))
      (node (ref "R3") (pin "1") (pinfunction "1_1") (pintype "passive"))
    )
    (net (code "119") (name "Net-(D13-PadA)") (class "Default")
      (node (ref "D13") (pin "A") (pinfunction "A_A") (pintype "passive"))
      (node (ref "RN2") (pin "1") (pinfunction "1_1") (pintype "passive"))
    )
    (net (code "120") (name "Net-(IC1-PadEN)") (class "Default")
      (node (ref "IC1") (pin "EN") (pinfunction "EN_EN") (pintype "bidirectional"))
      (node (ref "R4") (pin "2") (pinfunction "2_2") (pintype "passive"))
    )
    (net (code "121") (name "Net-(IC1-PadFB)") (class "Default")
      (node (ref "IC1") (pin "FB") (pinfunction "FB_FB") (pintype "bidirectional"))
      (node (ref "R10") (pin "2") (pinfunction "2_2") (pintype "passive"))
      (node (ref "R9") (pin "1") (pinfunction "1_1") (pintype "passive"))
    )
    (net (code "122") (name "Net-(PWR1-PadA)") (class "Default")
      (node (ref "PWR1") (pin "A") (pinfunction "A_A") (pintype "passive"))
      (node (ref "R12") (pin "2") (pinfunction "2_2") (pintype "passive"))
    )
    (net (code "123") (name "Net-(R5-Pad1)") (class "Default")
      (node (ref "R5") (pin "1") (pinfunction "1_1") (pintype "passive"))
      (node (ref "SJ1") (pin "2") (pinfunction "2_2") (pintype "passive"))
      (node (ref "U$6") (pin "MS1") (pinfunction "MS1_MS1") (pintype "input"))
    )
    (net (code "124") (name "Net-(RN1-Pad1)") (class "Default")
      (node (ref "RN1") (pin "1") (pinfunction "1_1") (pintype "passive"))
      (node (ref "SJ7") (pin "2") (pinfunction "2_2") (pintype "passive"))
      (node (ref "U$1") (pin "MS1") (pinfunction "MS1_MS1") (pintype "input"))
    )
    (net (code "125") (name "Net-(RN1B-1)") (class "Default")
      (node (ref "RN1") (pin "2") (pinfunction "1_2") (pintype "passive"))
      (node (ref "SJ3") (pin "2") (pinfunction "2_2") (pintype "passive"))
      (node (ref "U$7") (pin "MS1") (pinfunction "MS1_MS1") (pintype "input"))
    )
    (net (code "126") (name "Net-(RN1C-2)") (class "Default")
      (node (ref "A_STP") (pin "A") (pinfunction "A_A") (pintype "passive"))
      (node (ref "RN1") (pin "6") (pinfunction "2_6") (pintype "passive"))
    )
    (net (code "127") (name "Net-(RN1D-2)") (class "Default")
      (node (ref "B_STP") (pin "A") (pinfunction "A_A") (pintype "passive"))
      (node (ref "RN1") (pin "5") (pinfunction "2_5") (pintype "passive"))
    )
    (net (code "128") (name "Net-(RN2B-1)") (class "Default")
      (node (ref "RN2") (pin "2") (pinfunction "1_2") (pintype "passive"))
      (node (ref "RX_LED") (pin "C") (pinfunction "C_C") (pintype "passive"))
    )
    (net (code "129") (name "Net-(RN2C-1)") (class "Default")
      (node (ref "RN2") (pin "3") (pinfunction "1_3") (pintype "passive"))
      (node (ref "TX_LED") (pin "C") (pinfunction "C_C") (pintype "passive"))
    )
    (net (code "130") (name "Net-(RN2D-1)") (class "Default")
      (node (ref "PWR") (pin "A") (pinfunction "A_A") (pintype "passive"))
      (node (ref "RN2") (pin "4") (pinfunction "1_4") (pintype "passive"))
    )
    (net (code "131") (name "Net-(SJ2-Pad2)") (class "Default")
      (node (ref "SJ2") (pin "2") (pinfunction "2_2") (pintype "passive"))
      (node (ref "U$6") (pin "MS2") (pinfunction "MS2_MS2") (pintype "input"))
    )
    (net (code "132") (name "Net-(SJ4-Pad2)") (class "Default")
      (node (ref "SJ4") (pin "2") (pinfunction "2_2") (pintype "passive"))
      (node (ref "U$7") (pin "MS2") (pinfunction "MS2_MS2") (pintype "input"))
    )
    (net (code "133") (name "Net-(SJ5-Pad2)") (class "Default")
      (node (ref "SJ5") (pin "2") (pinfunction "2_2") (pintype "passive"))
      (node (ref "U$6") (pin "MS3") (pinfunction "MS3_MS3") (pintype "input"))
    )
    (net (code "134") (name "Net-(SJ6-Pad2)") (class "Default")
      (node (ref "SJ6") (pin "2") (pinfunction "2_2") (pintype "passive"))
      (node (ref "U$7") (pin "MS3") (pinfunction "MS3_MS3") (pintype "input"))
    )
    (net (code "135") (name "Net-(SJ8-Pad2)") (class "Default")
      (node (ref "SJ8") (pin "2") (pinfunction "2_2") (pintype "passive"))
      (node (ref "U$1") (pin "MS2") (pinfunction "MS2_MS2") (pintype "input"))
    )
    (net (code "136") (name "Net-(SJ9-Pad2)") (class "Default")
      (node (ref "SJ9") (pin "2") (pinfunction "2_2") (pintype "passive"))
      (node (ref "U$1") (pin "MS3") (pinfunction "MS3_MS3") (pintype "input"))
    )
    (net (code "137") (name "Net-(U$1-SLEEP)") (class "Default")
      (node (ref "U$1") (pin "RST") (pinfunction "RST_RST") (pintype "input"))
      (node (ref "U$1") (pin "SLP") (pinfunction "SLEEP_SLP") (pintype "input"))
    )
    (net (code "138") (name "Net-(U$6-SLEEP)") (class "Default")
      (node (ref "U$6") (pin "RST") (pinfunction "RST_RST") (pintype "input"))
      (node (ref "U$6") (pin "SLP") (pinfunction "SLEEP_SLP") (pintype "input"))
    )
    (net (code "139") (name "Net-(U$7-SLEEP)") (class "Default")
      (node (ref "U$7") (pin "RST") (pinfunction "RST_RST") (pintype "input"))
      (node (ref "U$7") (pin "SLP") (pinfunction "SLEEP_SLP") (pintype "input"))
    )
    (net (code "140") (name "VCC") (class "Default")
      (node (ref "D2") (pin "C") (pinfunction "C_C") (pintype "passive"))
      (node (ref "IC5") (pin "20") (pinfunction "VCC_20") (pintype "power_in"))
      (node (ref "R18") (pin "1") (pinfunction "1_1") (pintype "passive"))
      (node (ref "R19") (pin "1") (pinfunction "1_1") (pintype "passive"))
      (node (ref "R2") (pin "1") (pinfunction "1_1") (pintype "passive"))
      (node (ref "RN2") (pin "5") (pinfunction "2_5") (pintype "passive"))
      (node (ref "RX_LED") (pin "A") (pinfunction "A_A") (pintype "passive"))
      (node (ref "SER1") (pin "2") (pinfunction "2_2") (pintype "passive"))
      (node (ref "SER2") (pin "2") (pinfunction "2_2") (pintype "passive"))
      (node (ref "SJ1") (pin "1") (pinfunction "1_1") (pintype "passive"))
      (node (ref "SJ2") (pin "1") (pinfunction "1_1") (pintype "passive"))
      (node (ref "SJ3") (pin "1") (pinfunction "1_1") (pintype "passive"))
      (node (ref "SJ4") (pin "1") (pinfunction "1_1") (pintype "passive"))
      (node (ref "SJ5") (pin "1") (pinfunction "1_1") (pintype "passive"))
      (node (ref "SJ6") (pin "1") (pinfunction "1_1") (pintype "passive"))
      (node (ref "SJ7") (pin "1") (pinfunction "1_1") (pintype "passive"))
      (node (ref "SJ8") (pin "1") (pinfunction "1_1") (pintype "passive"))
      (node (ref "SJ9") (pin "1") (pinfunction "1_1") (pintype "passive"))
      (node (ref "TFT") (pin "3") (pinfunction "3_3") (pintype "passive"))
      (node (ref "TX_LED") (pin "A") (pinfunction "A_A") (pintype "passive"))
      (node (ref "U$1") (pin "VDD") (pinfunction "VDD_VDD") (pintype "power_in"))
      (node (ref "U$6") (pin "VDD") (pinfunction "VDD_VDD") (pintype "power_in"))
      (node (ref "U$7") (pin "VDD") (pinfunction "VDD_VDD") (pintype "power_in"))
      (node (ref "U1") (pin "5V@0") (pinfunction "5V_5V@0") (pintype "power_in"))
      (node (ref "U1") (pin "5V@1") (pinfunction "5V_5V@1") (pintype "power_in"))
      (node (ref "U1") (pin "5V@2") (pinfunction "5V_5V@2") (pintype "power_in"))
      (node (ref "X-MAX") (pin "2") (pinfunction "2_2") (pintype "passive"))
      (node (ref "X-MIN") (pin "2") (pinfunction "2_2") (pintype "passive"))
      (node (ref "Y-MAX") (pin "2") (pinfunction "2_2") (pintype "passive"))
      (node (ref "Y-MIN") (pin "2") (pinfunction "2_2") (pintype "passive"))
    )
    (net (code "141") (name "unconnected-(IC3A-Y3-Pad16)") (class "Default")
      (node (ref "IC3") (pin "16") (pinfunction "Y3_16") (pintype "tri_state"))
    )
    (net (code "142") (name "unconnected-(IC3A-Y4-Pad15)") (class "Default")
      (node (ref "IC3") (pin "15") (pinfunction "Y4_15") (pintype "tri_state"))
    )
    (net (code "143") (name "unconnected-(IC3A-Y5-Pad14)") (class "Default")
      (node (ref "IC3") (pin "14") (pinfunction "Y5_14") (pintype "tri_state"))
    )
    (net (code "144") (name "unconnected-(IC3A-Y6-Pad13)") (class "Default")
      (node (ref "IC3") (pin "13") (pinfunction "Y6_13") (pintype "tri_state"))
    )
    (net (code "145") (name "unconnected-(IC3A-Y8-Pad11)") (class "Default")
      (node (ref "IC3") (pin "11") (pinfunction "Y8_11") (pintype "tri_state"))
    )
    (net (code "146") (name "unconnected-(IC4A-Y8-Pad11)") (class "Default")
      (node (ref "IC4") (pin "11") (pinfunction "Y8_11") (pintype "tri_state"))
    )
    (net (code "147") (name "unconnected-(IC5A-Y1-Pad18)") (class "Default")
      (node (ref "IC5") (pin "18") (pinfunction "Y1_18") (pintype "tri_state"))
    )
    (net (code "148") (name "unconnected-(IC5A-Y5-Pad14)") (class "Default")
      (node (ref "IC5") (pin "14") (pinfunction "Y5_14") (pintype "tri_state"))
    )
    (net (code "149") (name "unconnected-(IC5A-Y6-Pad13)") (class "Default")
      (node (ref "IC5") (pin "13") (pinfunction "Y6_13") (pintype "tri_state"))
    )
    (net (code "150") (name "unconnected-(IC5A-Y7-Pad12)") (class "Default")
      (node (ref "IC5") (pin "12") (pinfunction "Y7_12") (pintype "tri_state"))
    )
    (net (code "151") (name "unconnected-(IC5A-Y8-Pad11)") (class "Default")
      (node (ref "IC5") (pin "11") (pinfunction "Y8_11") (pintype "tri_state"))
    )
    (net (code "152") (name "unconnected-(TFT-Pad5)") (class "Default")
      (node (ref "TFT") (pin "5") (pinfunction "5_5") (pintype "passive"))
    )
    (net (code "153") (name "unconnected-(TFT-Pad24)") (class "Default")
      (node (ref "TFT") (pin "24") (pinfunction "24_24") (pintype "passive"))
    )
    (net (code "154") (name "unconnected-(TFT-Pad31)") (class "Default")
      (node (ref "TFT") (pin "31") (pinfunction "31_31") (pintype "passive"))
    )
    (net (code "155") (name "unconnected-(TFT-Pad35)") (class "Default")
      (node (ref "TFT") (pin "35") (pinfunction "35_35") (pintype "passive"))
    )
    (net (code "156") (name "unconnected-(TFT-Pad38)") (class "Default")
      (node (ref "TFT") (pin "38") (pinfunction "38_38") (pintype "passive"))
    )
    (net (code "157") (name "unconnected-(TFT-Pad39)") (class "Default")
      (node (ref "TFT") (pin "39") (pinfunction "39_39") (pintype "passive"))
    )
    (net (code "158") (name "unconnected-(TFT-Pad40)") (class "Default")
      (node (ref "TFT") (pin "40") (pinfunction "40_40") (pintype "passive"))
    )
  )
)
